# dispenser_7_7.net
KiCad netlist of a schematic drawn in EAGLE
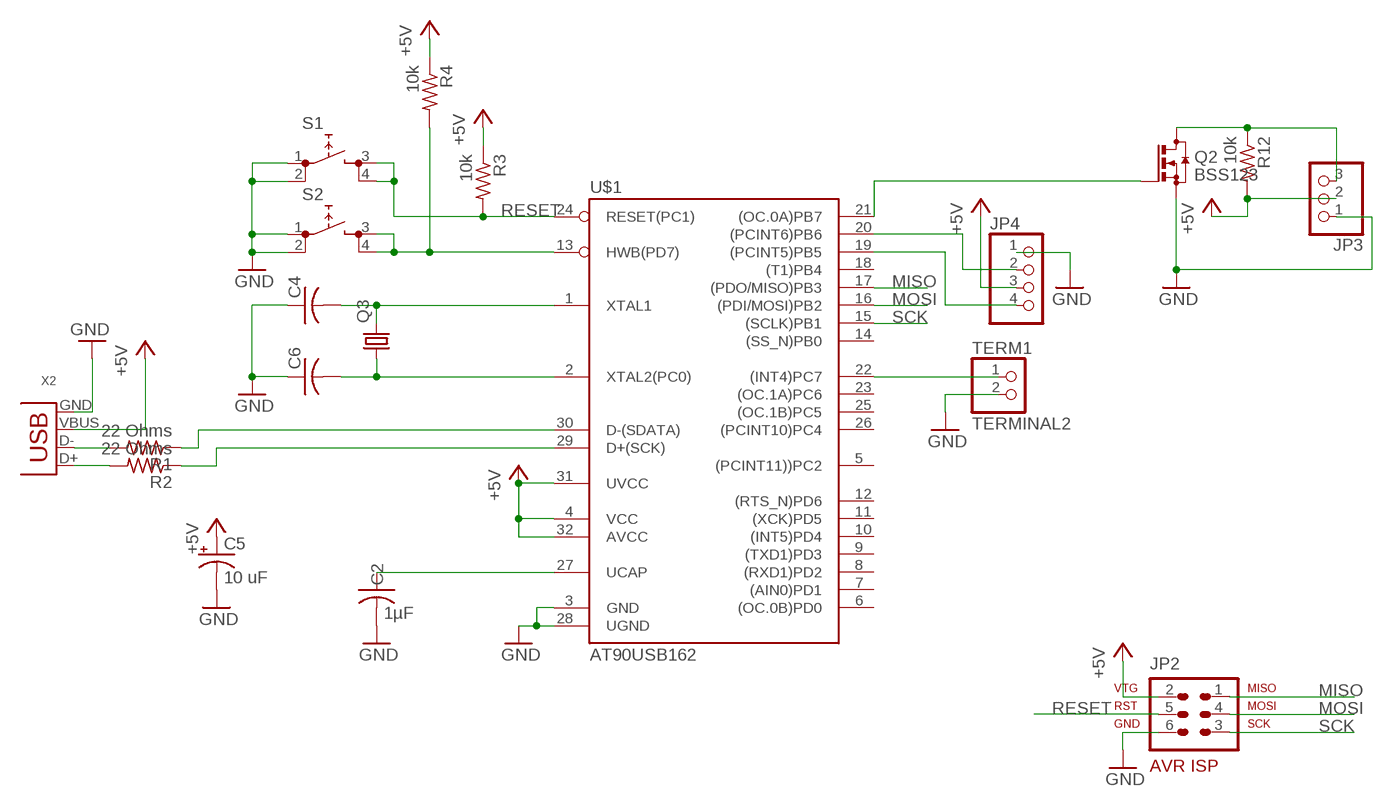
[diagram p0: schematic, sheet 1]

(export (version "E")
  (design (tool "Eeschema 10.0.6"))
  (components
    (comp (ref "C2")
      (value "1µF")
      (footprint "eagle-import:C050-025X075")
      (libsource (lib "eagle-import") (part "C-USC050-025X075"))
    )
    (comp (ref "C4")
      (value "C-USC050-025X075")
      (footprint "eagle-import:C050-025X075")
      (libsource (lib "eagle-import") (part "C-USC050-025X075"))
    )
    (comp (ref "C5")
      (value "10 uF")
      (footprint "eagle-import:E2,5-5")
      (libsource (lib "eagle-import") (part "CPOL-USE2.5-5"))
    )
    (comp (ref "C6")
      (value "C-USC050-025X075")
      (footprint "eagle-import:C050-025X075")
      (libsource (lib "eagle-import") (part "C-USC050-025X075"))
    )
    (comp (ref "JP2")
      (value "AVR-ISP-6")
      (footprint "eagle-import:AVR-ISP-6")
      (libsource (lib "eagle-import") (part "AVR-ISP-6"))
    )
    (comp (ref "JP3")
      (value "PINHD-1X3")
      (footprint "eagle-import:1X03")
      (libsource (lib "eagle-import") (part "PINHD-1X3"))
    )
    (comp (ref "JP4")
      (value "PINHD-1X4")
      (footprint "eagle-import:1X04")
      (libsource (lib "eagle-import") (part "PINHD-1X4"))
    )
    (comp (ref "Q2")
      (value "BSS123")
      (footprint "eagle-import:SOT23")
      (libsource (lib "eagle-import") (part "BSS123"))
    )
    (comp (ref "Q3")
      (value "CRYSTALHC49S")
      (footprint "eagle-import:HC49_S")
      (libsource (lib "eagle-import") (part "CRYSTALHC49S"))
    )
    (comp (ref "R1")
      (value "22 Ohms")
      (footprint "eagle-import:0207_7")
      (libsource (lib "eagle-import") (part "rcl@1_R-US_0207/7"))
    )
    (comp (ref "R2")
      (value "22 Ohms")
      (footprint "eagle-import:0207_7")
      (libsource (lib "eagle-import") (part "rcl@1_R-US_0207/7"))
    )
    (comp (ref "R3")
      (value "10k")
      (footprint "eagle-import:0207_7")
      (libsource (lib "eagle-import") (part "R-US_0207/7"))
    )
    (comp (ref "R4")
      (value "10k")
      (footprint "eagle-import:0207_7")
      (libsource (lib "eagle-import") (part "R-US_0207/7"))
    )
    (comp (ref "R12")
      (value "10k")
      (footprint "eagle-import:0207_7")
      (libsource (lib "eagle-import") (part "R-US_0207/7"))
    )
    (comp (ref "S1")
      (value "PUSHBUTTON")
      (footprint "eagle-import:TL1105SP")
      (libsource (lib "eagle-import") (part "PUSHBUTTON"))
    )
    (comp (ref "S2")
      (value "PUSHBUTTON")
      (footprint "eagle-import:TL1105SP")
      (libsource (lib "eagle-import") (part "PUSHBUTTON"))
    )
    (comp (ref "TERM1")
      (value "TERMINAL2")
      (footprint "eagle-import:TERM2")
      (libsource (lib "eagle-import") (part "TERMINAL2"))
    )
    (comp (ref "U$1")
      (value "AT90USB162")
      (footprint "eagle-import:TQFP32-08")
      (libsource (lib "eagle-import") (part "AT90USB162"))
    )
    (comp (ref "X2")
      (value "USB-MB-H")
      (footprint "eagle-import:USB-MB-H")
      (libsource (lib "eagle-import") (part "USB-MB-H"))
    )
  )
  (nets
    (net (code "1") (name "+5V") (class "Default")
      (node (ref "C5") (pin "+") (pinfunction "+_+") (pintype "passive"))
      (node (ref "JP2") (pin "2") (pinfunction "2_2") (pintype "passive"))
      (node (ref "JP3") (pin "2") (pinfunction "2_2") (pintype "passive"))
      (node (ref "JP4") (pin "3") (pinfunction "3_3") (pintype "passive"))
      (node (ref "R12") (pin "2") (pinfunction "2_2") (pintype "passive"))
      (node (ref "R3") (pin "1") (pinfunction "1_1") (pintype "passive"))
      (node (ref "R4") (pin "1") (pinfunction "1_1") (pintype "passive"))
      (node (ref "U$1") (pin "31") (pinfunction "UVCC_31") (pintype "power_in"))
      (node (ref "U$1") (pin "32") (pinfunction "AVCC_32") (pintype "power_in"))
      (node (ref "U$1") (pin "4") (pinfunction "VCC_4") (pintype "power_in"))
      (node (ref "X2") (pin "VBUS") (pinfunction "VBUS_VBUS") (pintype "bidirectional"))
    )
    (net (code "2") (name "/MISO") (class "Default")
      (node (ref "JP2") (pin "1") (pinfunction "1_1") (pintype "passive"))
      (node (ref "U$1") (pin "17") (pinfunction "(PDO/MISO)PB3_17") (pintype "bidirectional"))
    )
    (net (code "3") (name "/MOSI") (class "Default")
      (node (ref "JP2") (pin "4") (pinfunction "4_4") (pintype "passive"))
      (node (ref "U$1") (pin "16") (pinfunction "(PDI/MOSI)PB2_16") (pintype "bidirectional"))
    )
    (net (code "4") (name "/RESET") (class "Default")
      (node (ref "JP2") (pin "5") (pinfunction "5_5") (pintype "passive"))
      (node (ref "R3") (pin "2") (pinfunction "2_2") (pintype "passive"))
      (node (ref "S1") (pin "3") (pinfunction "1_3") (pintype "passive"))
      (node (ref "S1") (pin "4") (pinfunction "1_4") (pintype "passive"))
      (node (ref "U$1") (pin "24") (pinfunction "RESET(PC1)_24") (pintype "input"))
    )
    (net (code "5") (name "/SCK") (class "Default")
      (node (ref "JP2") (pin "3") (pinfunction "3_3") (pintype "passive"))
      (node (ref "U$1") (pin "15") (pinfunction "(SCLK)PB1_15") (pintype "bidirectional"))
    )
    (net (code "6") (name "GND") (class "Default")
      (node (ref "C2") (pin "2") (pinfunction "2_2") (pintype "passive"))
      (node (ref "C4") (pin "1") (pinfunction "1_1") (pintype "passive"))
      (node (ref "C5") (pin "-") (pinfunction "-_-") (pintype "passive"))
      (node (ref "C6") (pin "1") (pinfunction "1_1") (pintype "passive"))
      (node (ref "JP2") (pin "6") (pinfunction "6_6") (pintype "passive"))
      (node (ref "JP3") (pin "1") (pinfunction "1_1") (pintype "passive"))
      (node (ref "JP4") (pin "1") (pinfunction "1_1") (pintype "passive"))
      (node (ref "Q2") (pin "2") (pinfunction "S_2") (pintype "passive"))
      (node (ref "S1") (pin "1") (pinfunction "0_1") (pintype "passive"))
      (node (ref "S1") (pin "2") (pinfunction "0_2") (pintype "passive"))
      (node (ref "S2") (pin "1") (pinfunction "0_1") (pintype "passive"))
      (node (ref "S2") (pin "2") (pinfunction "0_2") (pintype "passive"))
      (node (ref "TERM1") (pin "2") (pinfunction "2_2") (pintype "passive"))
      (node (ref "U$1") (pin "28") (pinfunction "UGND_28") (pintype "power_in"))
      (node (ref "U$1") (pin "3") (pinfunction "GND_3") (pintype "power_in"))
      (node (ref "X2") (pin "GND") (pinfunction "GND_GND") (pintype "bidirectional"))
    )
    (net (code "7") (name "Net-(Q2-D)") (class "Default")
      (node (ref "JP3") (pin "3") (pinfunction "3_3") (pintype "passive"))
      (node (ref "Q2") (pin "3") (pinfunction "D_3") (pintype "passive"))
      (node (ref "R12") (pin "1") (pinfunction "1_1") (pintype "passive"))
    )
    (net (code "8") (name "Net-(Q2-G)") (class "Default")
      (node (ref "Q2") (pin "1") (pinfunction "G_1") (pintype "passive"))
      (node (ref "U$1") (pin "21") (pinfunction "(OC.0A)PB7_21") (pintype "bidirectional"))
    )
    (net (code "9") (name "Net-(R1-Pad2)") (class "Default")
      (node (ref "R1") (pin "2") (pinfunction "2_2") (pintype "passive"))
      (node (ref "X2") (pin "D-") (pinfunction "D-_D-") (pintype "bidirectional"))
    )
    (net (code "10") (name "Net-(R2-Pad2)") (class "Default")
      (node (ref "R2") (pin "2") (pinfunction "2_2") (pintype "passive"))
      (node (ref "X2") (pin "D+") (pinfunction "D+_D+") (pintype "bidirectional"))
    )
    (net (code "11") (name "Net-(U$1-(INT4)PC7)") (class "Default")
      (node (ref "TERM1") (pin "1") (pinfunction "1_1") (pintype "passive"))
      (node (ref "U$1") (pin "22") (pinfunction "(INT4)PC7_22") (pintype "bidirectional"))
    )
    (net (code "12") (name "Net-(U$1-(PCINT5)PB5)") (class "Default")
      (node (ref "JP4") (pin "4") (pinfunction "4_4") (pintype "passive"))
      (node (ref "U$1") (pin "19") (pinfunction "(PCINT5)PB5_19") (pintype "bidirectional"))
    )
    (net (code "13") (name "Net-(U$1-(PCINT6)PB6)") (class "Default")
      (node (ref "JP4") (pin "2") (pinfunction "2_2") (pintype "passive"))
      (node (ref "U$1") (pin "20") (pinfunction "(PCINT6)PB6_20") (pintype "bidirectional"))
    )
    (net (code "14") (name "Net-(U$1-D+(SCK))") (class "Default")
      (node (ref "R2") (pin "1") (pinfunction "1_1") (pintype "passive"))
      (node (ref "U$1") (pin "29") (pinfunction "D+(SCK)_29") (pintype "bidirectional"))
    )
    (net (code "15") (name "Net-(U$1-D-(SDATA))") (class "Default")
      (node (ref "R1") (pin "1") (pinfunction "1_1") (pintype "passive"))
      (node (ref "U$1") (pin "30") (pinfunction "D-(SDATA)_30") (pintype "bidirectional"))
    )
    (net (code "16") (name "Net-(U$1-HWB(PD7))") (class "Default")
      (node (ref "R4") (pin "2") (pinfunction "2_2") (pintype "passive"))
      (node (ref "S2") (pin "3") (pinfunction "1_3") (pintype "passive"))
      (node (ref "S2") (pin "4") (pinfunction "1_4") (pintype "passive"))
      (node (ref "U$1") (pin "13") (pinfunction "HWB(PD7)_13") (pintype "bidirectional"))
    )
    (net (code "17") (name "Net-(U$1-UCAP)") (class "Default")
      (node (ref "C2") (pin "1") (pinfunction "1_1") (pintype "passive"))
      (node (ref "U$1") (pin "27") (pinfunction "UCAP_27") (pintype "bidirectional"))
    )
    (net (code "18") (name "Net-(U$1-XTAL1)") (class "Default")
      (node (ref "C4") (pin "2") (pinfunction "2_2") (pintype "passive"))
      (node (ref "Q3") (pin "2") (pinfunction "2_2") (pintype "passive"))
      (node (ref "U$1") (pin "1") (pinfunction "XTAL1_1") (pintype "bidirectional"))
    )
    (net (code "19") (name "Net-(U$1-XTAL2(PC0))") (class "Default")
      (node (ref "C6") (pin "2") (pinfunction "2_2") (pintype "passive"))
      (node (ref "Q3") (pin "1") (pinfunction "1_1") (pintype "passive"))
      (node (ref "U$1") (pin "2") (pinfunction "XTAL2(PC0)_2") (pintype "bidirectional"))
    )
    (net (code "20") (name "unconnected-(U$1-(AIN0)PD1-Pad7)") (class "Default")
      (node (ref "U$1") (pin "7") (pinfunction "(AIN0)PD1_7") (pintype "bidirectional"))
    )
    (net (code "21") (name "unconnected-(U$1-(INT5)PD4-Pad10)") (class "Default")
      (node (ref "U$1") (pin "10") (pinfunction "(INT5)PD4_10") (pintype "bidirectional"))
    )
    (net (code "22") (name "unconnected-(U$1-(OC.0B)PD0-Pad6)") (class "Default")
      (node (ref "U$1") (pin "6") (pinfunction "(OC.0B)PD0_6") (pintype "bidirectional"))
    )
    (net (code "23") (name "unconnected-(U$1-(OC.1A)PC6-Pad23)") (class "Default")
      (node (ref "U$1") (pin "23") (pinfunction "(OC.1A)PC6_23") (pintype "bidirectional"))
    )
    (net (code "24") (name "unconnected-(U$1-(OC.1B)PC5-Pad25)") (class "Default")
      (node (ref "U$1") (pin "25") (pinfunction "(OC.1B)PC5_25") (pintype "bidirectional"))
    )
    (net (code "25") (name "unconnected-(U$1-(PCINT10)PC4-Pad26)") (class "Default")
      (node (ref "U$1") (pin "26") (pinfunction "(PCINT10)PC4_26") (pintype "bidirectional"))
    )
    (net (code "26") (name "unconnected-(U$1-(PCINT11))PC2-Pad5)") (class "Default")
      (node (ref "U$1") (pin "5") (pinfunction "(PCINT11))PC2_5") (pintype "bidirectional"))
    )
    (net (code "27") (name "unconnected-(U$1-(RTS_N)PD6-Pad12)") (class "Default")
      (node (ref "U$1") (pin "12") (pinfunction "(RTS_N)PD6_12") (pintype "bidirectional"))
    )
    (net (code "28") (name "unconnected-(U$1-(RXD1)PD2-Pad8)") (class "Default")
      (node (ref "U$1") (pin "8") (pinfunction "(RXD1)PD2_8") (pintype "bidirectional"))
    )
    (net (code "29") (name "unconnected-(U$1-(SS_N)PB0-Pad14)") (class "Default")
      (node (ref "U$1") (pin "14") (pinfunction "(SS_N)PB0_14") (pintype "bidirectional"))
    )
    (net (code "30") (name "unconnected-(U$1-(T1)PB4-Pad18)") (class "Default")
      (node (ref "U$1") (pin "18") (pinfunction "(T1)PB4_18") (pintype "bidirectional"))
    )
    (net (code "31") (name "unconnected-(U$1-(TXD1)PD3-Pad9)") (class "Default")
      (node (ref "U$1") (pin "9") (pinfunction "(TXD1)PD3_9") (pintype "bidirectional"))
    )
    (net (code "32") (name "unconnected-(U$1-(XCK)PD5-Pad11)") (class "Default")
      (node (ref "U$1") (pin "11") (pinfunction "(XCK)PD5_11") (pintype "bidirectional"))
    )
  )
)
